# connector_button.net
KiCad netlist of a schematic drawn in Altium Designer
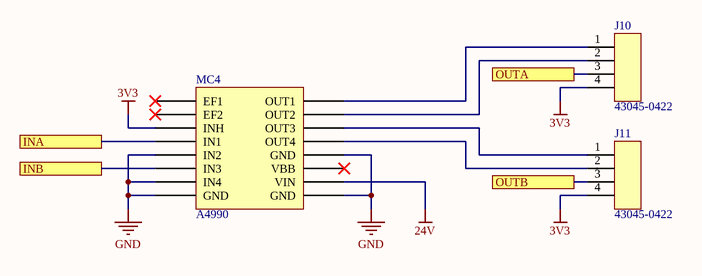
[diagram p0: connector_button.SchDoc]

(export (version "E")
  (design (tool "Eeschema 10.0.6"))
  (components
    (comp (ref "J10")
      (value "CONN_MOLEX_MICROFIT_DOUBLE_ROW_RA_TH_4POS_LOCK")
      (footprint "MOLEX_MICROFIT_DOUBLE_ROW_RA_TH_4POS_43045-0422")
      (description "CONN MOLEX MICROFIT 4POS RA GOLD")
      (fields (field (name "MFG") "Molex Inc") (field (name "MFG P/N") "43045-0422"))
      (libsource (lib "AltiumReleaseLibDB") (part "CONN_MOLEX_MICROFIT_DOUBLE_ROW_RA_TH_4POS_LOCK"))
    )
    (comp (ref "J11")
      (value "CONN_MOLEX_MICROFIT_DOUBLE_ROW_RA_TH_4POS_LOCK")
      (footprint "MOLEX_MICROFIT_DOUBLE_ROW_RA_TH_4POS_43045-0422")
      (description "CONN MOLEX MICROFIT 4POS RA GOLD")
      (fields (field (name "MFG") "Molex Inc") (field (name "MFG P/N") "43045-0422"))
      (libsource (lib "AltiumReleaseLibDB") (part "CONN_MOLEX_MICROFIT_DOUBLE_ROW_RA_TH_4POS_LOCK"))
    )
    (comp (ref "MC4")
      (value "A4990")
      (footprint "A4990 Dual Motor Driver Carrier")
      (libsource (lib "brew_lib") (part "A4990 Dual Motor Driver Carrier"))
    )
  )
  (nets
    (net (code "1") (name "/INA") (class "Default")
      (node (ref "MC4") (pin "4") (pinfunction "IN1_4") (pintype "passive"))
    )
    (net (code "2") (name "/INB") (class "Default")
      (node (ref "MC4") (pin "6") (pinfunction "IN3_6") (pintype "passive"))
    )
    (net (code "3") (name "/OUTA") (class "Default")
      (node (ref "J10") (pin "3") (pinfunction "3_3") (pintype "passive"))
    )
    (net (code "4") (name "/OUTB") (class "Default")
      (node (ref "J11") (pin "3") (pinfunction "3_3") (pintype "passive"))
    )
    (net (code "5") (name "3V3") (class "Default")
      (node (ref "J10") (pin "4") (pinfunction "4_4") (pintype "passive"))
      (node (ref "J11") (pin "4") (pinfunction "4_4") (pintype "passive"))
      (node (ref "MC4") (pin "3") (pinfunction "INH_3") (pintype "passive"))
    )
    (net (code "6") (name "24V") (class "Default")
      (node (ref "MC4") (pin "10") (pinfunction "VIN_10") (pintype "passive"))
    )
    (net (code "7") (name "GND") (class "Default")
      (node (ref "MC4") (pin "12") (pinfunction "GND_12") (pintype "passive"))
      (node (ref "MC4") (pin "5") (pinfunction "IN2_5") (pintype "passive"))
      (node (ref "MC4") (pin "7") (pinfunction "IN4_7") (pintype "passive"))
      (node (ref "MC4") (pin "8") (pinfunction "GND_8") (pintype "passive"))
      (node (ref "MC4") (pin "9") (pinfunction "GND_9") (pintype "passive"))
    )
    (net (code "8") (name "Net-(MC4-OUT1)") (class "Default")
      (node (ref "J10") (pin "1") (pinfunction "1_1") (pintype "passive"))
      (node (ref "MC4") (pin "16") (pinfunction "OUT1_16") (pintype "passive"))
    )
    (net (code "9") (name "Net-(MC4-OUT2)") (class "Default")
      (node (ref "J10") (pin "2") (pinfunction "2_2") (pintype "passive"))
      (node (ref "MC4") (pin "15") (pinfunction "OUT2_15") (pintype "passive"))
    )
    (net (code "10") (name "Net-(MC4-OUT3)") (class "Default")
      (node (ref "J11") (pin "1") (pinfunction "1_1") (pintype "passive"))
      (node (ref "MC4") (pin "14") (pinfunction "OUT3_14") (pintype "passive"))
    )
    (net (code "11") (name "Net-(MC4-OUT4)") (class "Default")
      (node (ref "J11") (pin "2") (pinfunction "2_2") (pintype "passive"))
      (node (ref "MC4") (pin "13") (pinfunction "OUT4_13") (pintype "passive"))
    )
    (net (code "12") (name "unconnected-(MC4-EF1-Pad1)") (class "Default")
      (node (ref "MC4") (pin "1") (pinfunction "EF1_1") (pintype "passive+no_connect"))
    )
    (net (code "13") (name "unconnected-(MC4-EF2-Pad2)") (class "Default")
      (node (ref "MC4") (pin "2") (pinfunction "EF2_2") (pintype "passive+no_connect"))
    )
    (net (code "14") (name "unconnected-(MC4-VBB-Pad11)") (class "Default")
      (node (ref "MC4") (pin "11") (pinfunction "VBB_11") (pintype "passive+no_connect"))
    )
  )
)
